# design.net
KiCad netlist of a schematic drawn in Altium Designer
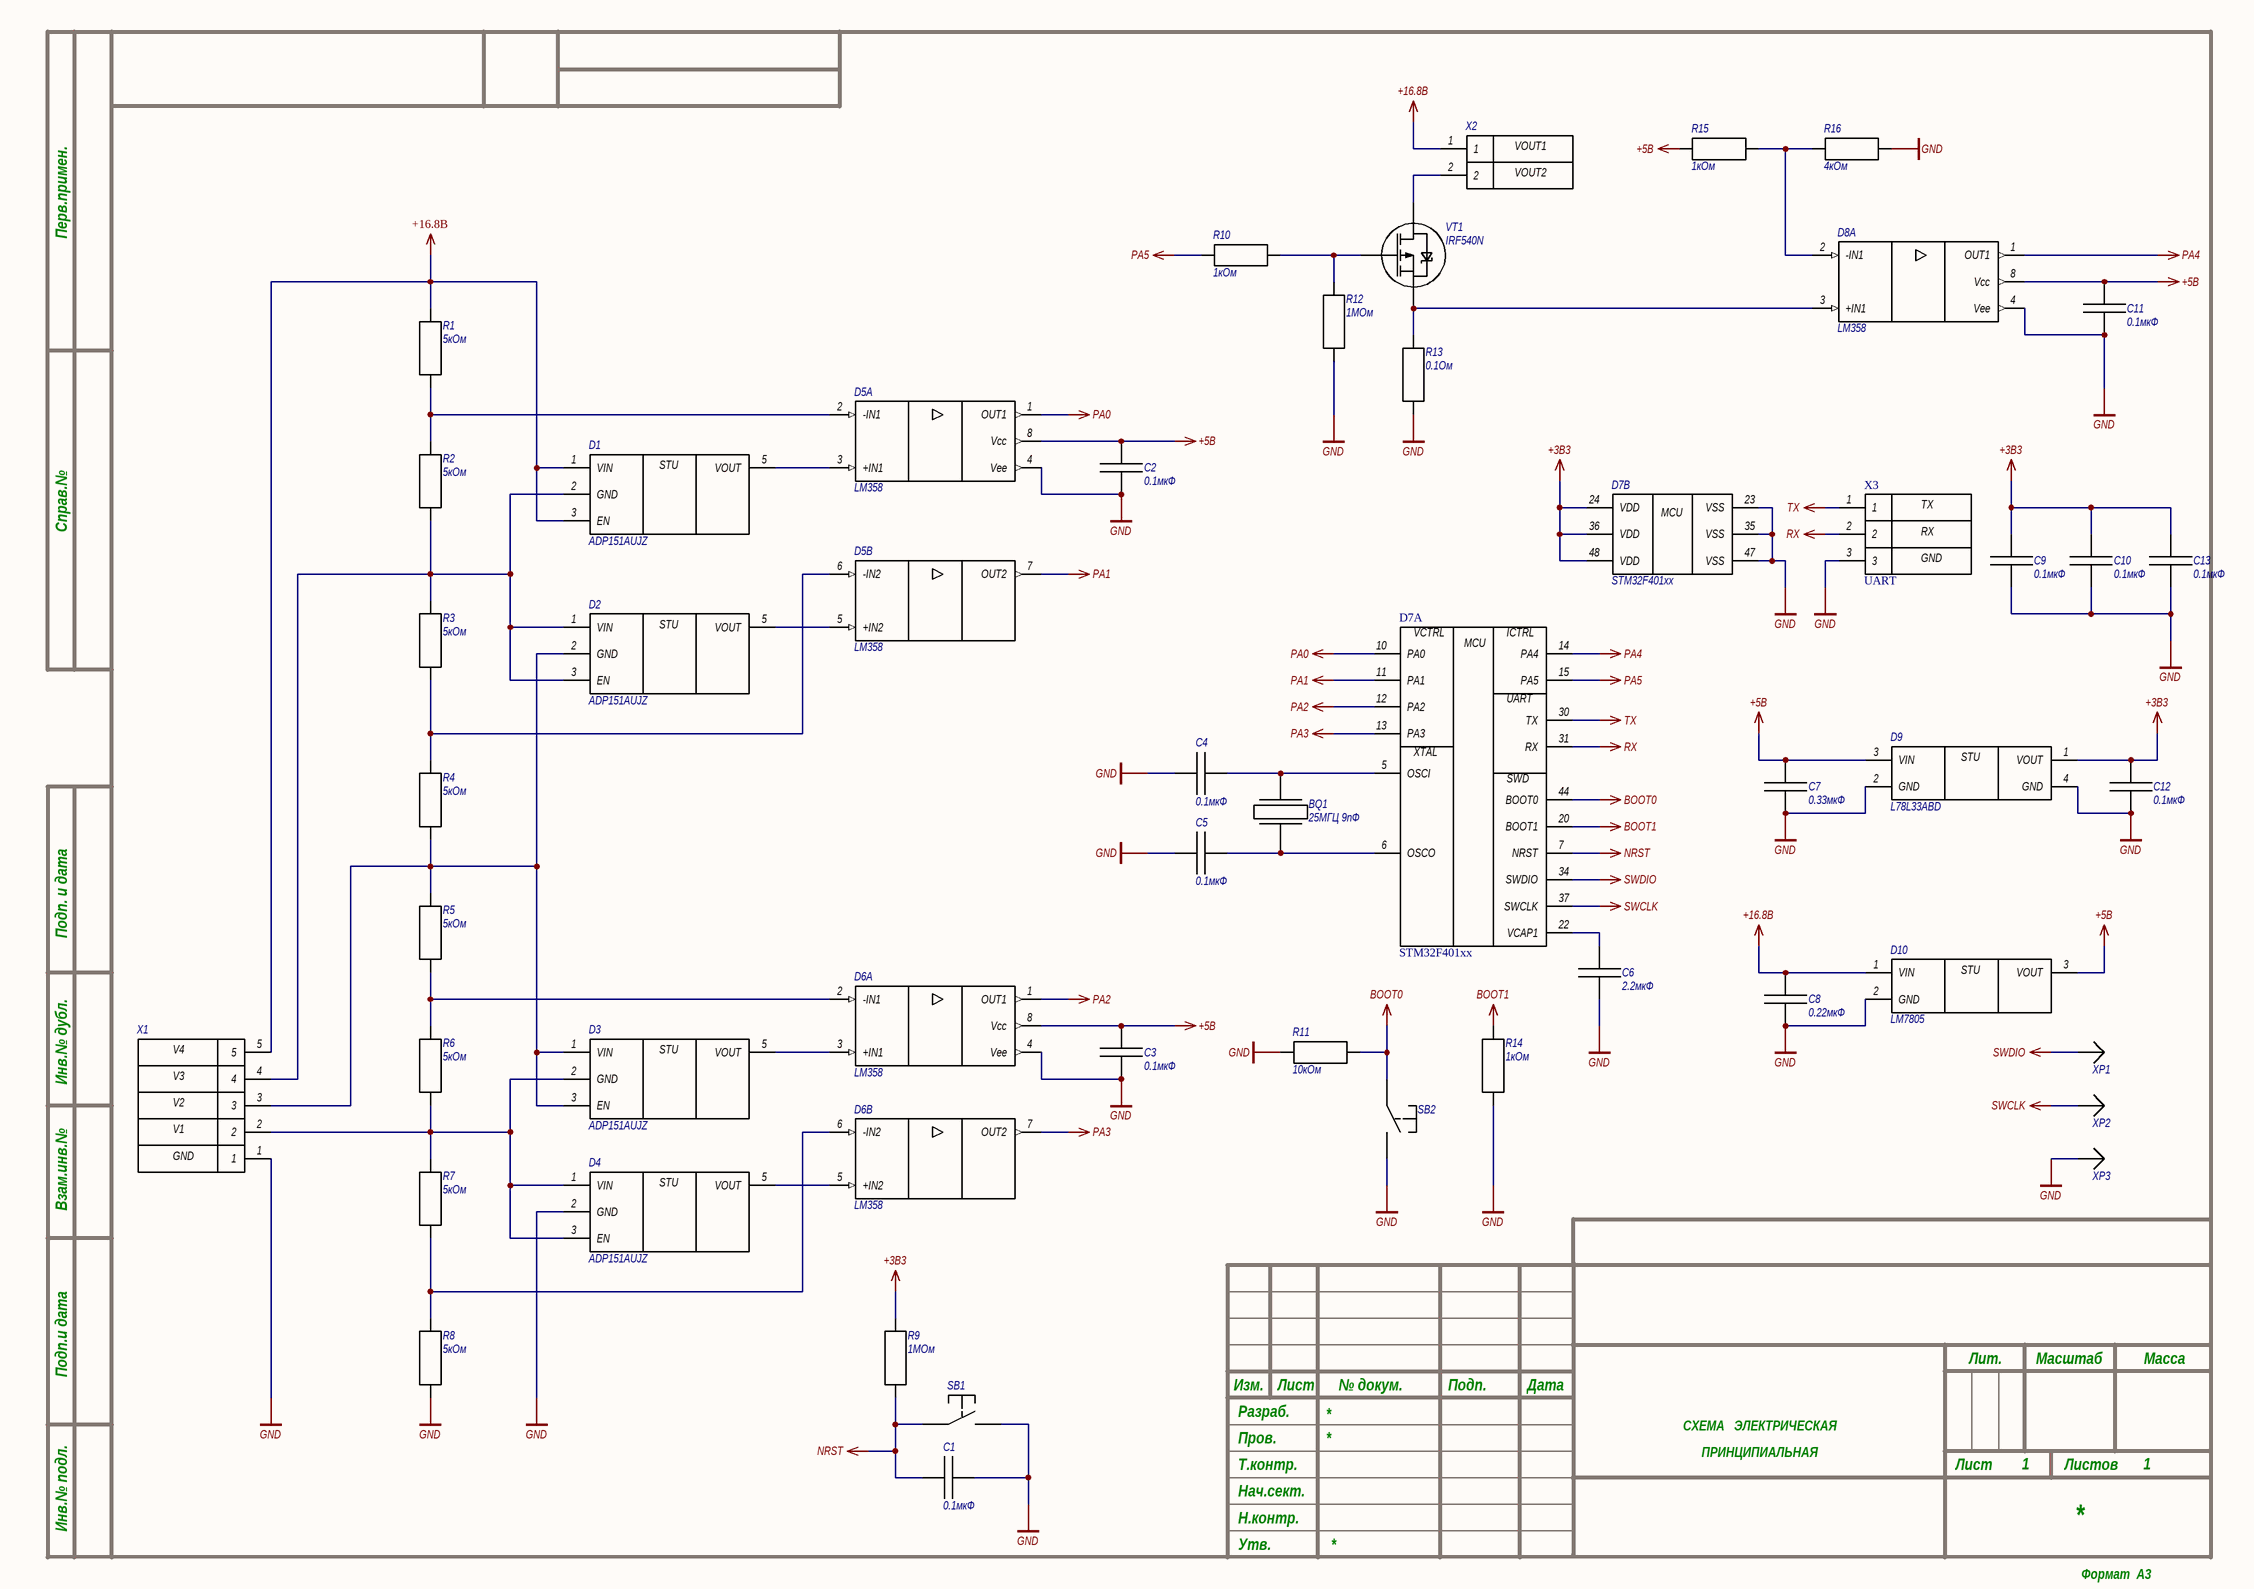
[diagram p0: Задание.SchDoc]

(export (version "E")
  (design (tool "Eeschema 10.0.6"))
  (components
    (comp (ref "BQ1") (value "25МГЦ 9пФ") (libsource (lib "Schlib1") (part "Resonator")))
    (comp (ref "C1")
      (value "0.1мкФ")
      (footprint "CAPC2012L-С0805")
      (description "планарный конденсатор")
      (libsource (lib "IDNP-new") (part "C0805"))
    )
    (comp (ref "C2")
      (value "0.1мкФ")
      (footprint "CAPC2012L-С0805")
      (description "планарный конденсатор")
      (libsource (lib "IDNP-new") (part "C0805"))
    )
    (comp (ref "C3")
      (value "0.1мкФ")
      (footprint "CAPC2012L-С0805")
      (description "планарный конденсатор")
      (libsource (lib "IDNP-new") (part "C0805"))
    )
    (comp (ref "C4")
      (value "0.1мкФ")
      (footprint "CAPC2012L-С0805")
      (description "планарный конденсатор")
      (libsource (lib "IDNP-new") (part "C0805"))
    )
    (comp (ref "C5")
      (value "0.1мкФ")
      (footprint "CAPC2012L-С0805")
      (description "планарный конденсатор")
      (libsource (lib "IDNP-new") (part "C0805"))
    )
    (comp (ref "C6")
      (value "2.2мкФ")
      (footprint "CAPC2012L-С0805")
      (description "планарный конденсатор")
      (libsource (lib "IDNP-new") (part "C0805"))
    )
    (comp (ref "C7")
      (value "0.33мкФ")
      (footprint "CAPC2012L-С0805")
      (description "планарный конденсатор")
      (libsource (lib "IDNP-new") (part "C0805"))
    )
    (comp (ref "C8")
      (value "0.22мкФ")
      (footprint "CAPC2012L-С0805")
      (description "планарный конденсатор")
      (libsource (lib "IDNP-new") (part "C0805"))
    )
    (comp (ref "C9")
      (value "0.1мкФ")
      (footprint "CAPC2012L-С0805")
      (description "планарный конденсатор")
      (libsource (lib "IDNP-new") (part "C0805"))
    )
    (comp (ref "C10")
      (value "0.1мкФ")
      (footprint "CAPC2012L-С0805")
      (description "планарный конденсатор")
      (libsource (lib "IDNP-new") (part "C0805"))
    )
    (comp (ref "C11")
      (value "0.1мкФ")
      (footprint "CAPC2012L-С0805")
      (description "планарный конденсатор")
      (libsource (lib "IDNP-new") (part "C0805"))
    )
    (comp (ref "C12")
      (value "0.1мкФ")
      (footprint "CAPC2012L-С0805")
      (description "планарный конденсатор")
      (libsource (lib "IDNP-new") (part "C0805"))
    )
    (comp (ref "C13")
      (value "0.1мкФ")
      (footprint "CAPC2012L-С0805")
      (description "планарный конденсатор")
      (libsource (lib "IDNP-new") (part "C0805"))
    )
    (comp (ref "D1") (value "ADP151AUJZ") (libsource (lib "Schlib1") (part "ADP151AUJZ")))
    (comp (ref "D2") (value "ADP151AUJZ") (libsource (lib "Schlib1") (part "ADP151AUJZ")))
    (comp (ref "D3") (value "ADP151AUJZ") (libsource (lib "Schlib1") (part "ADP151AUJZ")))
    (comp (ref "D4") (value "ADP151AUJZ") (libsource (lib "Schlib1") (part "ADP151AUJZ")))
    (comp (ref "D5") (value "LM358") (libsource (lib "Schlib1") (part "LM358")))
    (comp (ref "D6") (value "LM358") (libsource (lib "Schlib1") (part "LM358")))
    (comp (ref "D7") (value "STM32F401xx") (libsource (lib "") (part "STM32F401xx_1")))
    (comp (ref "D8") (value "LM358") (libsource (lib "Schlib1") (part "LM358")))
    (comp (ref "D9") (value "L78L33ABD") (libsource (lib "Schlib1") (part "L78L33ABD")))
    (comp (ref "D10") (value "LM7805") (libsource (lib "Schlib1") (part "LM7805")))
    (comp (ref "R1") (value "5кОм") (libsource (lib "Schlib1") (part "Res")))
    (comp (ref "R2") (value "5кОм") (libsource (lib "Schlib1") (part "Res")))
    (comp (ref "R3") (value "5кОм") (libsource (lib "Schlib1") (part "Res")))
    (comp (ref "R4") (value "5кОм") (libsource (lib "Schlib1") (part "Res")))
    (comp (ref "R5") (value "5кОм") (libsource (lib "Schlib1") (part "Res")))
    (comp (ref "R6") (value "5кОм") (libsource (lib "Schlib1") (part "Res")))
    (comp (ref "R7") (value "5кОм") (libsource (lib "Schlib1") (part "Res")))
    (comp (ref "R8") (value "5кОм") (libsource (lib "Schlib1") (part "Res")))
    (comp (ref "R9") (value "1МОм") (libsource (lib "Schlib1") (part "Res")))
    (comp (ref "R10") (value "1кОм") (libsource (lib "Schlib1") (part "Res")))
    (comp (ref "R11") (value "10кОм") (libsource (lib "Schlib1") (part "Res")))
    (comp (ref "R12") (value "1МОм") (libsource (lib "Schlib1") (part "Res")))
    (comp (ref "R13") (value "0.1Ом") (libsource (lib "Schlib1") (part "Res")))
    (comp (ref "R14") (value "1кОм") (libsource (lib "Schlib1") (part "Res")))
    (comp (ref "R15") (value "1кОм") (libsource (lib "Schlib1") (part "Res")))
    (comp (ref "R16") (value "4кОм") (libsource (lib "Schlib1") (part "Res")))
    (comp (ref "SB1") (value "Button") (libsource (lib "Schlib1") (part "Button")))
    (comp (ref "SB2") (value "Button") (libsource (lib "Schlib1") (part "Button")))
    (comp (ref "VT1") (value "IRF540N") (libsource (lib "Schlib1") (part "IRF540N")))
    (comp (ref "X1") (value "Klem5") (libsource (lib "Schlib1") (part "Klem5")))
    (comp (ref "X2") (value "~") (libsource (lib "Schlib1") (part "Klem2")))
    (comp (ref "X3") (value "UART") (libsource (lib "Schlib1") (part "RX/TX")))
    (comp (ref "XP1") (value "PLS-1") (footprint "KlemmaD1") (libsource (lib "2017-LIB") (part "PLS-1")))
    (comp (ref "XP2") (value "PLS-1") (footprint "KlemmaD1") (libsource (lib "2017-LIB") (part "PLS-1")))
    (comp (ref "XP3") (value "PLS-1") (footprint "KlemmaD1") (libsource (lib "2017-LIB") (part "PLS-1")))
  )
  (nets
    (net (code "1") (name "+3В3") (class "Default")
      (node (ref "C10") (pin "1") (pinfunction "1_1") (pintype "passive"))
      (node (ref "C12") (pin "1") (pinfunction "1_1") (pintype "passive"))
      (node (ref "C13") (pin "1") (pinfunction "1_1") (pintype "passive"))
      (node (ref "C9") (pin "1") (pinfunction "1_1") (pintype "passive"))
      (node (ref "D7") (pin "24") (pinfunction "VDD_24") (pintype "passive"))
      (node (ref "D7") (pin "36") (pinfunction "VDD_36") (pintype "passive"))
      (node (ref "D7") (pin "48") (pinfunction "VDD_48") (pintype "passive"))
      (node (ref "D9") (pin "1") (pinfunction "VOUT_1") (pintype "passive"))
      (node (ref "R9") (pin "1") (pinfunction "1_1") (pintype "passive"))
    )
    (net (code "2") (name "+5В") (class "Default")
      (node (ref "C11") (pin "1") (pinfunction "1_1") (pintype "passive"))
      (node (ref "C2") (pin "1") (pinfunction "1_1") (pintype "passive"))
      (node (ref "C3") (pin "1") (pinfunction "1_1") (pintype "passive"))
      (node (ref "C7") (pin "1") (pinfunction "1_1") (pintype "passive"))
      (node (ref "D10") (pin "3") (pinfunction "VOUT_3") (pintype "passive"))
      (node (ref "D5") (pin "8") (pinfunction "Vcc_8") (pintype "output"))
      (node (ref "D6") (pin "8") (pinfunction "Vcc_8") (pintype "output"))
      (node (ref "D8") (pin "8") (pinfunction "Vcc_8") (pintype "output"))
      (node (ref "D9") (pin "3") (pinfunction "VIN_3") (pintype "passive"))
      (node (ref "R15") (pin "2") (pinfunction "2_2") (pintype "passive"))
    )
    (net (code "3") (name "+16.8В") (class "Default")
      (node (ref "C8") (pin "1") (pinfunction "1_1") (pintype "passive"))
      (node (ref "D1") (pin "1") (pinfunction "VIN_1") (pintype "passive"))
      (node (ref "D1") (pin "3") (pinfunction "EN_3") (pintype "passive"))
      (node (ref "D10") (pin "1") (pinfunction "VIN_1") (pintype "passive"))
      (node (ref "R1") (pin "1") (pinfunction "1_1") (pintype "passive"))
      (node (ref "X1") (pin "5") (pinfunction "5_5") (pintype "passive"))
      (node (ref "X2") (pin "1") (pinfunction "1_1") (pintype "passive"))
    )
    (net (code "4") (name "BOOT0") (class "Default")
      (node (ref "D7") (pin "44") (pinfunction "BOOT0_44") (pintype "passive"))
      (node (ref "R11") (pin "1") (pinfunction "1_1") (pintype "passive"))
      (node (ref "SB2") (pin "54") (pinfunction "54_54") (pintype "passive"))
    )
    (net (code "5") (name "BOOT1") (class "Default")
      (node (ref "D7") (pin "20") (pinfunction "BOOT1_20") (pintype "passive"))
      (node (ref "R14") (pin "1") (pinfunction "1_1") (pintype "passive"))
    )
    (net (code "6") (name "GND") (class "Default")
      (node (ref "C1") (pin "2") (pinfunction "2_2") (pintype "passive"))
      (node (ref "C10") (pin "2") (pinfunction "2_2") (pintype "passive"))
      (node (ref "C11") (pin "2") (pinfunction "2_2") (pintype "passive"))
      (node (ref "C12") (pin "2") (pinfunction "2_2") (pintype "passive"))
      (node (ref "C13") (pin "2") (pinfunction "2_2") (pintype "passive"))
      (node (ref "C2") (pin "2") (pinfunction "2_2") (pintype "passive"))
      (node (ref "C3") (pin "2") (pinfunction "2_2") (pintype "passive"))
      (node (ref "C4") (pin "1") (pinfunction "1_1") (pintype "passive"))
      (node (ref "C5") (pin "1") (pinfunction "1_1") (pintype "passive"))
      (node (ref "C6") (pin "2") (pinfunction "2_2") (pintype "passive"))
      (node (ref "C7") (pin "2") (pinfunction "2_2") (pintype "passive"))
      (node (ref "C8") (pin "2") (pinfunction "2_2") (pintype "passive"))
      (node (ref "C9") (pin "2") (pinfunction "2_2") (pintype "passive"))
      (node (ref "D10") (pin "2") (pinfunction "GND_2") (pintype "passive"))
      (node (ref "D4") (pin "2") (pinfunction "GND_2") (pintype "passive"))
      (node (ref "D5") (pin "4") (pinfunction "Vee_4") (pintype "output"))
      (node (ref "D6") (pin "4") (pinfunction "Vee_4") (pintype "output"))
      (node (ref "D7") (pin "23") (pinfunction "VSS_23") (pintype "passive"))
      (node (ref "D7") (pin "35") (pinfunction "VSS_35") (pintype "passive"))
      (node (ref "D7") (pin "47") (pinfunction "VSS_47") (pintype "passive"))
      (node (ref "D8") (pin "4") (pinfunction "Vee_4") (pintype "output"))
      (node (ref "D9") (pin "2") (pinfunction "GND_2") (pintype "passive"))
      (node (ref "D9") (pin "4") (pinfunction "GND_4") (pintype "passive"))
      (node (ref "R11") (pin "2") (pinfunction "2_2") (pintype "passive"))
      (node (ref "R12") (pin "2") (pinfunction "2_2") (pintype "passive"))
      (node (ref "R13") (pin "2") (pinfunction "2_2") (pintype "passive"))
      (node (ref "R14") (pin "2") (pinfunction "2_2") (pintype "passive"))
      (node (ref "R16") (pin "1") (pinfunction "1_1") (pintype "passive"))
      (node (ref "R8") (pin "2") (pinfunction "2_2") (pintype "passive"))
      (node (ref "SB1") (pin "55") (pinfunction "55_55") (pintype "passive"))
      (node (ref "SB2") (pin "55") (pinfunction "55_55") (pintype "passive"))
      (node (ref "X1") (pin "1") (pinfunction "1_1") (pintype "passive"))
      (node (ref "X3") (pin "3") (pinfunction "3_3") (pintype "passive"))
      (node (ref "XP3") (pin "1") (pinfunction "1_1") (pintype "passive"))
    )
    (net (code "7") (name "NRST") (class "Default")
      (node (ref "C1") (pin "1") (pinfunction "1_1") (pintype "passive"))
      (node (ref "D7") (pin "7") (pinfunction "NRST_7") (pintype "passive"))
      (node (ref "R9") (pin "2") (pinfunction "2_2") (pintype "passive"))
      (node (ref "SB1") (pin "54") (pinfunction "54_54") (pintype "passive"))
    )
    (net (code "8") (name "Net-(D1-GND)") (class "Default")
      (node (ref "D1") (pin "2") (pinfunction "GND_2") (pintype "passive"))
      (node (ref "D2") (pin "1") (pinfunction "VIN_1") (pintype "passive"))
      (node (ref "D2") (pin "3") (pinfunction "EN_3") (pintype "passive"))
      (node (ref "R2") (pin "2") (pinfunction "2_2") (pintype "passive"))
      (node (ref "R3") (pin "1") (pinfunction "1_1") (pintype "passive"))
      (node (ref "X1") (pin "4") (pinfunction "4_4") (pintype "passive"))
    )
    (net (code "9") (name "Net-(D1-VOUT)") (class "Default")
      (node (ref "D1") (pin "5") (pinfunction "VOUT_5") (pintype "passive"))
      (node (ref "D5") (pin "3") (pinfunction "+IN1_3") (pintype "input"))
    )
    (net (code "10") (name "Net-(D2-GND)") (class "Default")
      (node (ref "D2") (pin "2") (pinfunction "GND_2") (pintype "passive"))
      (node (ref "D3") (pin "1") (pinfunction "VIN_1") (pintype "passive"))
      (node (ref "D3") (pin "3") (pinfunction "EN_3") (pintype "passive"))
      (node (ref "R4") (pin "2") (pinfunction "2_2") (pintype "passive"))
      (node (ref "R5") (pin "1") (pinfunction "1_1") (pintype "passive"))
      (node (ref "X1") (pin "3") (pinfunction "3_3") (pintype "passive"))
    )
    (net (code "11") (name "Net-(D2-VOUT)") (class "Default")
      (node (ref "D2") (pin "5") (pinfunction "VOUT_5") (pintype "passive"))
      (node (ref "D5") (pin "5") (pinfunction "+IN2_5") (pintype "input"))
    )
    (net (code "12") (name "Net-(D3-GND)") (class "Default")
      (node (ref "D3") (pin "2") (pinfunction "GND_2") (pintype "passive"))
      (node (ref "D4") (pin "1") (pinfunction "VIN_1") (pintype "passive"))
      (node (ref "D4") (pin "3") (pinfunction "EN_3") (pintype "passive"))
      (node (ref "R6") (pin "2") (pinfunction "2_2") (pintype "passive"))
      (node (ref "R7") (pin "1") (pinfunction "1_1") (pintype "passive"))
      (node (ref "X1") (pin "2") (pinfunction "2_2") (pintype "passive"))
    )
    (net (code "13") (name "Net-(D3-VOUT)") (class "Default")
      (node (ref "D3") (pin "5") (pinfunction "VOUT_5") (pintype "passive"))
      (node (ref "D6") (pin "3") (pinfunction "+IN1_3") (pintype "input"))
    )
    (net (code "14") (name "Net-(D4-VOUT)") (class "Default")
      (node (ref "D4") (pin "5") (pinfunction "VOUT_5") (pintype "passive"))
      (node (ref "D6") (pin "5") (pinfunction "+IN2_5") (pintype "input"))
    )
    (net (code "15") (name "Net-(D5A--IN1)") (class "Default")
      (node (ref "D5") (pin "2") (pinfunction "-IN1_2") (pintype "input"))
      (node (ref "R1") (pin "2") (pinfunction "2_2") (pintype "passive"))
      (node (ref "R2") (pin "1") (pinfunction "1_1") (pintype "passive"))
    )
    (net (code "16") (name "Net-(D5B--IN2)") (class "Default")
      (node (ref "D5") (pin "6") (pinfunction "-IN2_6") (pintype "input"))
      (node (ref "R3") (pin "2") (pinfunction "2_2") (pintype "passive"))
      (node (ref "R4") (pin "1") (pinfunction "1_1") (pintype "passive"))
    )
    (net (code "17") (name "Net-(D6A--IN1)") (class "Default")
      (node (ref "D6") (pin "2") (pinfunction "-IN1_2") (pintype "input"))
      (node (ref "R5") (pin "2") (pinfunction "2_2") (pintype "passive"))
      (node (ref "R6") (pin "1") (pinfunction "1_1") (pintype "passive"))
    )
    (net (code "18") (name "Net-(D6B--IN2)") (class "Default")
      (node (ref "D6") (pin "6") (pinfunction "-IN2_6") (pintype "input"))
      (node (ref "R7") (pin "2") (pinfunction "2_2") (pintype "passive"))
      (node (ref "R8") (pin "1") (pinfunction "1_1") (pintype "passive"))
    )
    (net (code "19") (name "Net-(D7A-OSCI)") (class "Default")
      (node (ref "BQ1") (pin "53") (pinfunction "53_53") (pintype "passive"))
      (node (ref "C4") (pin "2") (pinfunction "2_2") (pintype "passive"))
      (node (ref "D7") (pin "5") (pinfunction "OSCI_5") (pintype "passive"))
    )
    (net (code "20") (name "Net-(D7A-OSCO)") (class "Default")
      (node (ref "BQ1") (pin "52") (pinfunction "52_52") (pintype "passive"))
      (node (ref "C5") (pin "2") (pinfunction "2_2") (pintype "passive"))
      (node (ref "D7") (pin "6") (pinfunction "OSCO_6") (pintype "passive"))
    )
    (net (code "21") (name "Net-(D7A-VCAP1)") (class "Default")
      (node (ref "C6") (pin "1") (pinfunction "1_1") (pintype "passive"))
      (node (ref "D7") (pin "22") (pinfunction "VCAP1_22") (pintype "passive"))
    )
    (net (code "22") (name "Net-(D8A-+IN1)") (class "Default")
      (node (ref "D8") (pin "3") (pinfunction "+IN1_3") (pintype "input"))
      (node (ref "R13") (pin "1") (pinfunction "1_1") (pintype "passive"))
      (node (ref "VT1") (pin "2") (pinfunction "S_2") (pintype "passive"))
    )
    (net (code "23") (name "Net-(D8A--IN1)") (class "Default")
      (node (ref "D8") (pin "2") (pinfunction "-IN1_2") (pintype "input"))
      (node (ref "R15") (pin "1") (pinfunction "1_1") (pintype "passive"))
      (node (ref "R16") (pin "2") (pinfunction "2_2") (pintype "passive"))
    )
    (net (code "24") (name "Net-(VT1-D)") (class "Default")
      (node (ref "VT1") (pin "3") (pinfunction "D_3") (pintype "passive"))
      (node (ref "X2") (pin "2") (pinfunction "2_2") (pintype "passive"))
    )
    (net (code "25") (name "Net-(VT1-G)") (class "Default")
      (node (ref "R10") (pin "1") (pinfunction "1_1") (pintype "passive"))
      (node (ref "R12") (pin "1") (pinfunction "1_1") (pintype "passive"))
      (node (ref "VT1") (pin "1") (pinfunction "G_1") (pintype "passive"))
    )
    (net (code "26") (name "PA0") (class "Default")
      (node (ref "D5") (pin "1") (pinfunction "OUT1_1") (pintype "output"))
      (node (ref "D7") (pin "10") (pinfunction "PA0_10") (pintype "passive"))
    )
    (net (code "27") (name "PA1") (class "Default")
      (node (ref "D5") (pin "7") (pinfunction "OUT2_7") (pintype "output"))
      (node (ref "D7") (pin "11") (pinfunction "PA1_11") (pintype "passive"))
    )
    (net (code "28") (name "PA2") (class "Default")
      (node (ref "D6") (pin "1") (pinfunction "OUT1_1") (pintype "output"))
      (node (ref "D7") (pin "12") (pinfunction "PA2_12") (pintype "passive"))
    )
    (net (code "29") (name "PA3") (class "Default")
      (node (ref "D6") (pin "7") (pinfunction "OUT2_7") (pintype "output"))
      (node (ref "D7") (pin "13") (pinfunction "PA3_13") (pintype "passive"))
    )
    (net (code "30") (name "PA4") (class "Default")
      (node (ref "D7") (pin "14") (pinfunction "PA4_14") (pintype "passive"))
      (node (ref "D8") (pin "1") (pinfunction "OUT1_1") (pintype "output"))
    )
    (net (code "31") (name "PA5") (class "Default")
      (node (ref "D7") (pin "15") (pinfunction "PA5_15") (pintype "passive"))
      (node (ref "R10") (pin "2") (pinfunction "2_2") (pintype "passive"))
    )
    (net (code "32") (name "RX") (class "Default")
      (node (ref "D7") (pin "31") (pinfunction "RX_31") (pintype "passive"))
      (node (ref "X3") (pin "2") (pinfunction "2_2") (pintype "passive"))
    )
    (net (code "33") (name "SWCLK") (class "Default")
      (node (ref "D7") (pin "37") (pinfunction "SWCLK_37") (pintype "passive"))
      (node (ref "XP2") (pin "1") (pinfunction "1_1") (pintype "passive"))
    )
    (net (code "34") (name "SWDIO") (class "Default")
      (node (ref "D7") (pin "34") (pinfunction "SWDIO_34") (pintype "passive"))
      (node (ref "XP1") (pin "1") (pinfunction "1_1") (pintype "passive"))
    )
    (net (code "35") (name "TX") (class "Default")
      (node (ref "D7") (pin "30") (pinfunction "TX_30") (pintype "passive"))
      (node (ref "X3") (pin "1") (pinfunction "1_1") (pintype "passive"))
    )
  )
)
